# Alti.net
KiCad netlist of a schematic drawn in EAGLE
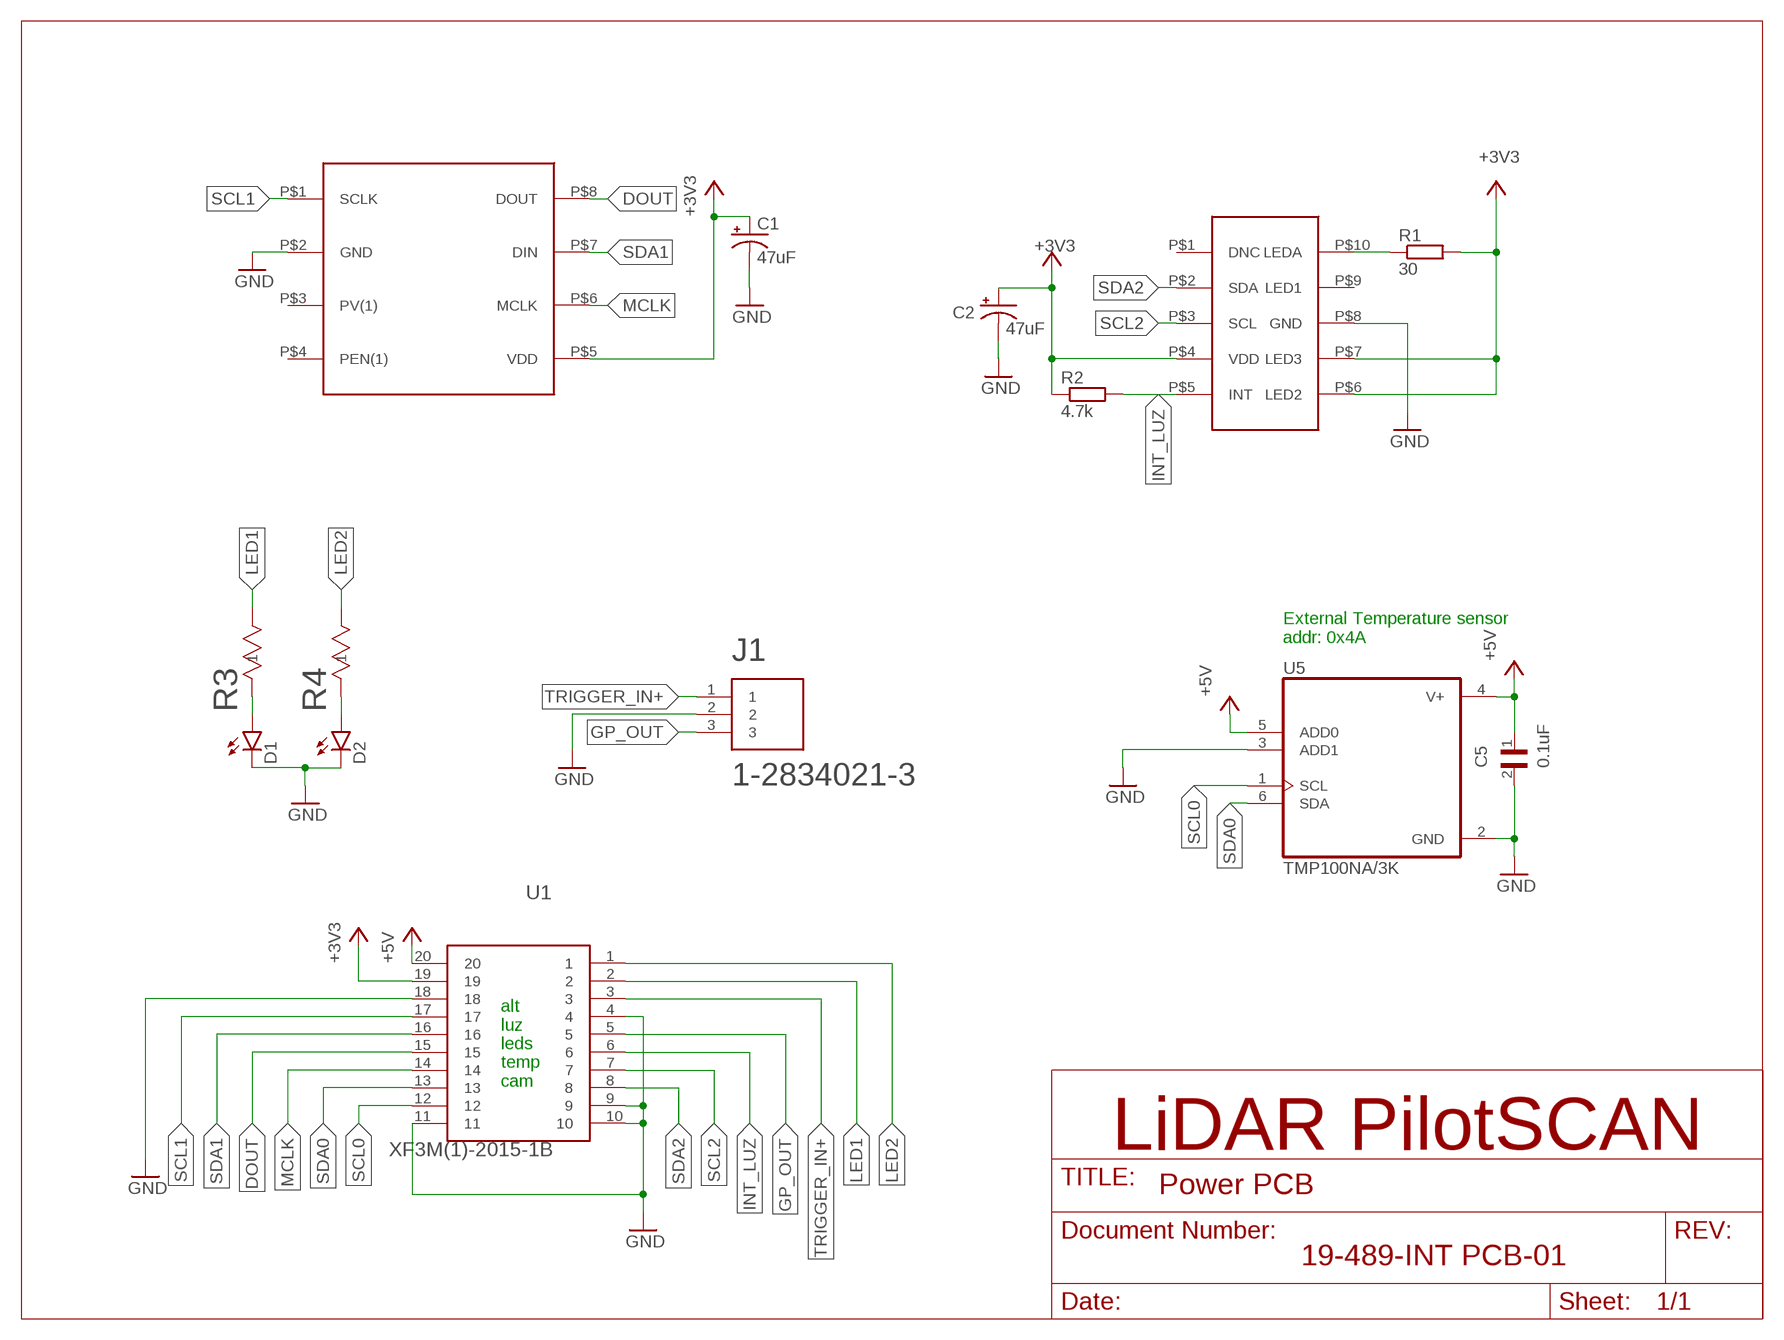
[diagram p0: schematic, sheet 1]

(export (version "E")
  (design (tool "Eeschema 10.0.6"))
  (components
    (comp (ref "C1")
      (value "47uF")
      (footprint "eagle-import:CL31A476MQHNNWE")
      (libsource (lib "eagle-import") (part "CL31A476MQHNNWE"))
    )
    (comp (ref "C2")
      (value "47uF")
      (footprint "eagle-import:CL31A476MQHNNWE")
      (libsource (lib "eagle-import") (part "CL31A476MQHNNWE"))
    )
    (comp (ref "C5")
      (value "0.1uF")
      (footprint "eagle-import:CAPC2012X140N")
      (fields (field (name "MF") "AVX") (field (name "MP") "08056C104JAZ2A"))
      (libsource (lib "eagle-import") (part "08056C104JAZ2A"))
    )
    (comp (ref "D1")
      (value "TLMS1000-GS08")
      (footprint "eagle-import:RESC1608X55")
      (fields (field (name "DIGI-KEY_PART_NUMBER") "TLMS1000-GS08CT-ND") (field (name "MF") "Vishay"))
      (libsource (lib "eagle-import") (part "TLMS1000-GS08"))
    )
    (comp (ref "D2")
      (value "TLMS1000-GS08")
      (footprint "eagle-import:RESC1608X55")
      (fields (field (name "DIGI-KEY_PART_NUMBER") "TLMS1000-GS08CT-ND") (field (name "MF") "Vishay"))
      (libsource (lib "eagle-import") (part "TLMS1000-GS08"))
    )
    (comp (ref "J1")
      (value "1-2834021-3")
      (footprint "eagle-import:CONN_1-2834021-3")
      (fields (field (name "DIGI-KEY_PART_NUMBER") "A123845-ND") (field (name "MF") "TE Connectivity"))
      (libsource (lib "eagle-import") (part "1-2834021-3"))
    )
    (comp (ref "R1")
      (value "30")
      (footprint "eagle-import:1812X7R")
      (libsource (lib "eagle-import") (part "R-EU_1812X7R"))
    )
    (comp (ref "R2")
      (value "4.7k")
      (footprint "eagle-import:RMCF0805FT4K70")
      (libsource (lib "eagle-import") (part "RMCF0805FT4K70"))
    )
    (comp (ref "R3")
      (value "RC0201JR-071K8L")
      (footprint "eagle-import:RES_RC0201_P6XP3")
      (fields (field (name "MANUFACTURER_PART_NUMBER") "RC0201JR071K8L"))
      (libsource (lib "eagle-import") (part "RC0201JR-071K8L"))
    )
    (comp (ref "R4")
      (value "RC0201JR-071K8L")
      (footprint "eagle-import:RES_RC0201_P6XP3")
      (fields (field (name "MANUFACTURER_PART_NUMBER") "RC0201JR071K8L"))
      (libsource (lib "eagle-import") (part "RC0201JR-071K8L"))
    )
    (comp (ref "U1")
      (value "XF3M(1)-2015-1B")
      (footprint "eagle-import:XF3M(1)-2015-1B")
      (fields (field (name "MF") "Molex") (field (name "MP") "52207-1485"))
      (libsource (lib "eagle-import") (part "XF3M(1)-2015-1B"))
    )
    (comp (ref "U2")
      (value "325540009-50")
      (footprint "eagle-import:325540009-50")
      (libsource (lib "eagle-import") (part "325540009-50"))
    )
    (comp (ref "U3")
      (value "SI1147-M01-GM")
      (footprint "eagle-import:SI1147-M01-GM")
      (libsource (lib "eagle-import") (part "SI1147-M01-GM"))
    )
    (comp (ref "U5")
      (value "TMP100NA/3K")
      (footprint "eagle-import:TMP100NA_3K")
      (fields (field (name "MF") "Texas Instruments"))
      (libsource (lib "eagle-import") (part "TMP100NA/3K"))
    )
  )
  (nets
    (net (code "1") (name "+3V3") (class "Default")
      (node (ref "C1") (pin "2") (pinfunction "+_2") (pintype "passive"))
      (node (ref "C2") (pin "2") (pinfunction "+_2") (pintype "passive"))
      (node (ref "R1") (pin "2") (pinfunction "2_2") (pintype "passive"))
      (node (ref "R2") (pin "1") (pinfunction "1_1") (pintype "passive"))
      (node (ref "U1") (pin "19") (pinfunction "19_19") (pintype "bidirectional"))
      (node (ref "U2") (pin "P$5") (pinfunction "VDD_P$5") (pintype "bidirectional"))
      (node (ref "U3") (pin "P$4") (pinfunction "VDD_P$4") (pintype "bidirectional"))
      (node (ref "U3") (pin "P$6") (pinfunction "LED2_P$6") (pintype "bidirectional"))
      (node (ref "U3") (pin "P$7") (pinfunction "LED3_P$7") (pintype "bidirectional"))
    )
    (net (code "2") (name "+5V") (class "Default")
      (node (ref "C5") (pin "1") (pinfunction "1_1") (pintype "passive"))
      (node (ref "U1") (pin "20") (pinfunction "20_20") (pintype "bidirectional"))
      (node (ref "U5") (pin "4") (pinfunction "V+_4") (pintype "power_in"))
      (node (ref "U5") (pin "5") (pinfunction "ADD0_5") (pintype "input"))
    )
    (net (code "3") (name "DOUT") (class "Default")
      (node (ref "U1") (pin "15") (pinfunction "15_15") (pintype "bidirectional"))
      (node (ref "U2") (pin "P$8") (pinfunction "DOUT_P$8") (pintype "bidirectional"))
    )
    (net (code "4") (name "GND") (class "Default")
      (node (ref "C1") (pin "1") (pinfunction "-_1") (pintype "passive"))
      (node (ref "C2") (pin "1") (pinfunction "-_1") (pintype "passive"))
      (node (ref "C5") (pin "2") (pinfunction "2_2") (pintype "passive"))
      (node (ref "D1") (pin "2") (pinfunction "C_2") (pintype "passive"))
      (node (ref "D2") (pin "2") (pinfunction "C_2") (pintype "passive"))
      (node (ref "J1") (pin "2") (pinfunction "2_2") (pintype "passive"))
      (node (ref "U1") (pin "10") (pinfunction "10_10") (pintype "bidirectional"))
      (node (ref "U1") (pin "11") (pinfunction "11_11") (pintype "bidirectional"))
      (node (ref "U1") (pin "18") (pinfunction "18_18") (pintype "bidirectional"))
      (node (ref "U1") (pin "4") (pinfunction "4_4") (pintype "bidirectional"))
      (node (ref "U1") (pin "9") (pinfunction "9_9") (pintype "bidirectional"))
      (node (ref "U2") (pin "P$2") (pinfunction "GND_P$2") (pintype "bidirectional"))
      (node (ref "U3") (pin "P$8") (pinfunction "GND_P$8") (pintype "bidirectional"))
      (node (ref "U5") (pin "2") (pinfunction "GND_2") (pintype "power_in"))
      (node (ref "U5") (pin "3") (pinfunction "ADD1_3") (pintype "input"))
    )
    (net (code "5") (name "GP_OUT") (class "Default")
      (node (ref "J1") (pin "3") (pinfunction "3_3") (pintype "passive"))
      (node (ref "U1") (pin "5") (pinfunction "5_5") (pintype "bidirectional"))
    )
    (net (code "6") (name "INT_LUZ") (class "Default")
      (node (ref "R2") (pin "2") (pinfunction "2_2") (pintype "passive"))
      (node (ref "U1") (pin "6") (pinfunction "6_6") (pintype "bidirectional"))
      (node (ref "U3") (pin "P$5") (pinfunction "INT_P$5") (pintype "bidirectional"))
    )
    (net (code "7") (name "LED1") (class "Default")
      (node (ref "R3") (pin "2") (pinfunction "2_2") (pintype "passive"))
      (node (ref "U1") (pin "2") (pinfunction "2_2") (pintype "bidirectional"))
    )
    (net (code "8") (name "LED2") (class "Default")
      (node (ref "R4") (pin "2") (pinfunction "2_2") (pintype "passive"))
      (node (ref "U1") (pin "1") (pinfunction "1_1") (pintype "bidirectional"))
    )
    (net (code "9") (name "MCLK") (class "Default")
      (node (ref "U1") (pin "14") (pinfunction "14_14") (pintype "bidirectional"))
      (node (ref "U2") (pin "P$6") (pinfunction "MCLK_P$6") (pintype "bidirectional"))
    )
    (net (code "10") (name "Net-(D1-A)") (class "Default")
      (node (ref "D1") (pin "1") (pinfunction "A_1") (pintype "passive"))
      (node (ref "R3") (pin "1") (pinfunction "1_1") (pintype "passive"))
    )
    (net (code "11") (name "Net-(D2-A)") (class "Default")
      (node (ref "D2") (pin "1") (pinfunction "A_1") (pintype "passive"))
      (node (ref "R4") (pin "1") (pinfunction "1_1") (pintype "passive"))
    )
    (net (code "12") (name "Net-(U3-LEDA)") (class "Default")
      (node (ref "R1") (pin "1") (pinfunction "1_1") (pintype "passive"))
      (node (ref "U3") (pin "P$10") (pinfunction "LEDA_P$10") (pintype "bidirectional"))
    )
    (net (code "13") (name "SCL0") (class "Default")
      (node (ref "U1") (pin "12") (pinfunction "12_12") (pintype "bidirectional"))
      (node (ref "U5") (pin "1") (pinfunction "SCL_1") (pintype "input"))
    )
    (net (code "14") (name "SCL1") (class "Default")
      (node (ref "U1") (pin "17") (pinfunction "17_17") (pintype "bidirectional"))
      (node (ref "U2") (pin "P$1") (pinfunction "SCLK_P$1") (pintype "bidirectional"))
    )
    (net (code "15") (name "SCL2") (class "Default")
      (node (ref "U1") (pin "7") (pinfunction "7_7") (pintype "bidirectional"))
      (node (ref "U3") (pin "P$3") (pinfunction "SCL_P$3") (pintype "bidirectional"))
    )
    (net (code "16") (name "SDA0") (class "Default")
      (node (ref "U1") (pin "13") (pinfunction "13_13") (pintype "bidirectional"))
      (node (ref "U5") (pin "6") (pinfunction "SDA_6") (pintype "bidirectional"))
    )
    (net (code "17") (name "SDA1") (class "Default")
      (node (ref "U1") (pin "16") (pinfunction "16_16") (pintype "bidirectional"))
      (node (ref "U2") (pin "P$7") (pinfunction "DIN_P$7") (pintype "bidirectional"))
    )
    (net (code "18") (name "SDA2") (class "Default")
      (node (ref "U1") (pin "8") (pinfunction "8_8") (pintype "bidirectional"))
      (node (ref "U3") (pin "P$2") (pinfunction "SDA_P$2") (pintype "bidirectional"))
    )
    (net (code "19") (name "TRIGGER_IN+") (class "Default")
      (node (ref "J1") (pin "1") (pinfunction "1_1") (pintype "passive"))
      (node (ref "U1") (pin "3") (pinfunction "3_3") (pintype "bidirectional"))
    )
    (net (code "20") (name "unconnected-(U2-PEN(1)-PadP$4)") (class "Default")
      (node (ref "U2") (pin "P$4") (pinfunction "PEN(1)_P$4") (pintype "bidirectional"))
    )
    (net (code "21") (name "unconnected-(U2-PV(1)-PadP$3)") (class "Default")
      (node (ref "U2") (pin "P$3") (pinfunction "PV(1)_P$3") (pintype "bidirectional"))
    )
    (net (code "22") (name "unconnected-(U3-DNC-PadP$1)") (class "Default")
      (node (ref "U3") (pin "P$1") (pinfunction "DNC_P$1") (pintype "bidirectional"))
    )
    (net (code "23") (name "unconnected-(U3-LED1-PadP$9)") (class "Default")
      (node (ref "U3") (pin "P$9") (pinfunction "LED1_P$9") (pintype "bidirectional"))
    )
  )
)
